# 3-AUDIO-AMP.net
KiCad netlist of a schematic drawn in Altium Designer
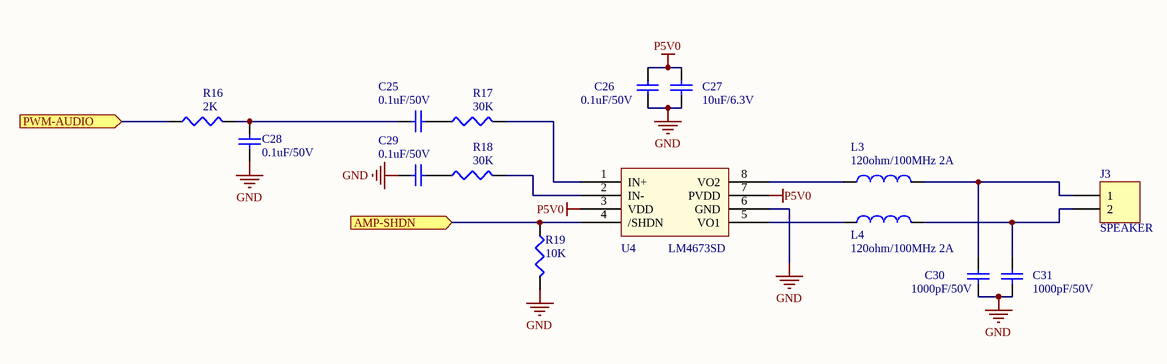
[diagram p0: 3-AUDIO-AMP.SchDoc]

(export (version "E")
  (design (tool "Eeschema 10.0.6"))
  (components
    (comp (ref "C25")
      (value "0.1uF/50V")
      (footprint "0402")
      (description "Capacitor")
      (fields (field (name "PUBLISHER") "Altium Limited"))
      (libsource (lib "Miscellaneous Devices") (part "Cap"))
    )
    (comp (ref "C26")
      (value "0.1uF/50V")
      (footprint "0402")
      (description "Capacitor")
      (fields (field (name "PUBLISHER") "Altium Limited"))
      (libsource (lib "Miscellaneous Devices") (part "Cap"))
    )
    (comp (ref "C27")
      (value "10uF/6.3V")
      (footprint "0603")
      (description "Capacitor")
      (fields (field (name "PUBLISHER") "Altium Limited"))
      (libsource (lib "Miscellaneous Devices") (part "Cap"))
    )
    (comp (ref "C28")
      (value "0.1uF/50V")
      (footprint "0402")
      (description "Capacitor")
      (fields (field (name "PUBLISHER") "Altium Limited"))
      (libsource (lib "Miscellaneous Devices") (part "Cap"))
    )
    (comp (ref "C29")
      (value "0.1uF/50V")
      (footprint "0402")
      (description "Capacitor")
      (fields (field (name "PUBLISHER") "Altium Limited"))
      (libsource (lib "Miscellaneous Devices") (part "Cap"))
    )
    (comp (ref "C30")
      (value "1000pF/50V")
      (footprint "0402")
      (description "Capacitor")
      (fields (field (name "PUBLISHER") "Altium Limited"))
      (libsource (lib "Miscellaneous Devices") (part "Cap"))
    )
    (comp (ref "C31")
      (value "1000pF/50V")
      (footprint "0402")
      (description "Capacitor")
      (fields (field (name "PUBLISHER") "Altium Limited"))
      (libsource (lib "Miscellaneous Devices") (part "Cap"))
    )
    (comp (ref "J3")
      (value "SPEAKER")
      (footprint "1250WV-S-2P")
      (description "Header, 2-Pin")
      (fields (field (name "PUBLISHER") "Altium Limited"))
      (libsource (lib "Miscellaneous Connectors") (part "Header 2"))
    )
    (comp (ref "L3")
      (value "120ohm/100MHz 2A")
      (footprint "0603")
      (description "Inductor")
      (fields (field (name "PUBLISHER") "Altium Limited"))
      (libsource (lib "Miscellaneous Devices") (part "Inductor"))
    )
    (comp (ref "L4")
      (value "120ohm/100MHz 2A")
      (footprint "0603")
      (description "Inductor")
      (fields (field (name "PUBLISHER") "Altium Limited"))
      (libsource (lib "Miscellaneous Devices") (part "Inductor"))
    )
    (comp (ref "R16")
      (value "2K")
      (footprint "0402")
      (description "Resistor")
      (fields (field (name "PUBLISHER") "Altium Limited"))
      (libsource (lib "Miscellaneous Devices") (part "Res3"))
    )
    (comp (ref "R17")
      (value "30K")
      (footprint "0402")
      (description "Resistor")
      (fields (field (name "PUBLISHER") "Altium Limited"))
      (libsource (lib "Miscellaneous Devices") (part "Res3"))
    )
    (comp (ref "R18")
      (value "30K")
      (footprint "0402")
      (description "Resistor")
      (fields (field (name "PUBLISHER") "Altium Limited"))
      (libsource (lib "Miscellaneous Devices") (part "Res3"))
    )
    (comp (ref "R19")
      (value "10K")
      (footprint "0402")
      (description "Resistor")
      (fields (field (name "PUBLISHER") "Altium Limited"))
      (libsource (lib "Miscellaneous Devices") (part "Res3"))
    )
    (comp (ref "U4") (value "LM4673SD") (footprint "WSON8") (libsource (lib "Schlib") (part "LM4673SD")))
  )
  (nets
    (net (code "1") (name "/AMP-SHDN") (class "Default")
      (node (ref "R19") (pin "1") (pinfunction "1_1") (pintype "passive"))
      (node (ref "U4") (pin "4") (pinfunction "/SHDN_4") (pintype "passive"))
    )
    (net (code "2") (name "/PWM-AUDIO") (class "Default")
      (node (ref "R16") (pin "1") (pinfunction "1_1") (pintype "passive"))
    )
    (net (code "3") (name "GND") (class "Default")
      (node (ref "C26") (pin "1") (pinfunction "1_1") (pintype "passive"))
      (node (ref "C27") (pin "1") (pinfunction "1_1") (pintype "passive"))
      (node (ref "C28") (pin "2") (pinfunction "2_2") (pintype "passive"))
      (node (ref "C29") (pin "2") (pinfunction "2_2") (pintype "passive"))
      (node (ref "C30") (pin "1") (pinfunction "1_1") (pintype "passive"))
      (node (ref "C31") (pin "1") (pinfunction "1_1") (pintype "passive"))
      (node (ref "R19") (pin "2") (pinfunction "2_2") (pintype "passive"))
      (node (ref "U4") (pin "6") (pinfunction "GND_6") (pintype "passive"))
    )
    (net (code "4") (name "Net-(C25-Pad1)") (class "Default")
      (node (ref "C25") (pin "1") (pinfunction "1_1") (pintype "passive"))
      (node (ref "R17") (pin "1") (pinfunction "1_1") (pintype "passive"))
    )
    (net (code "5") (name "Net-(C25-Pad2)") (class "Default")
      (node (ref "C25") (pin "2") (pinfunction "2_2") (pintype "passive"))
      (node (ref "C28") (pin "1") (pinfunction "1_1") (pintype "passive"))
      (node (ref "R16") (pin "2") (pinfunction "2_2") (pintype "passive"))
    )
    (net (code "6") (name "Net-(C29-Pad1)") (class "Default")
      (node (ref "C29") (pin "1") (pinfunction "1_1") (pintype "passive"))
      (node (ref "R18") (pin "1") (pinfunction "1_1") (pintype "passive"))
    )
    (net (code "7") (name "Net-(C30-Pad2)") (class "Default")
      (node (ref "C30") (pin "2") (pinfunction "2_2") (pintype "passive"))
      (node (ref "J3") (pin "1") (pinfunction "1_1") (pintype "passive"))
      (node (ref "L3") (pin "2") (pinfunction "2_2") (pintype "passive"))
    )
    (net (code "8") (name "Net-(C31-Pad2)") (class "Default")
      (node (ref "C31") (pin "2") (pinfunction "2_2") (pintype "passive"))
      (node (ref "J3") (pin "2") (pinfunction "2_2") (pintype "passive"))
      (node (ref "L4") (pin "2") (pinfunction "2_2") (pintype "passive"))
    )
    (net (code "9") (name "Net-(U4-IN+)") (class "Default")
      (node (ref "R17") (pin "2") (pinfunction "2_2") (pintype "passive"))
      (node (ref "U4") (pin "1") (pinfunction "IN+_1") (pintype "passive"))
    )
    (net (code "10") (name "Net-(U4-IN-)") (class "Default")
      (node (ref "R18") (pin "2") (pinfunction "2_2") (pintype "passive"))
      (node (ref "U4") (pin "2") (pinfunction "IN-_2") (pintype "passive"))
    )
    (net (code "11") (name "Net-(U4-VO1)") (class "Default")
      (node (ref "L4") (pin "1") (pinfunction "1_1") (pintype "passive"))
      (node (ref "U4") (pin "5") (pinfunction "VO1_5") (pintype "passive"))
    )
    (net (code "12") (name "Net-(U4-VO2)") (class "Default")
      (node (ref "L3") (pin "1") (pinfunction "1_1") (pintype "passive"))
      (node (ref "U4") (pin "8") (pinfunction "VO2_8") (pintype "passive"))
    )
    (net (code "13") (name "P5V0") (class "Default")
      (node (ref "C26") (pin "2") (pinfunction "2_2") (pintype "passive"))
      (node (ref "C27") (pin "2") (pinfunction "2_2") (pintype "passive"))
      (node (ref "U4") (pin "3") (pinfunction "VDD_3") (pintype "passive"))
      (node (ref "U4") (pin "7") (pinfunction "PVDD_7") (pintype "passive"))
    )
  )
)
